# Own_USB-C_Breakout_v3_0_Final_AR.net
KiCad netlist of a schematic drawn in EAGLE
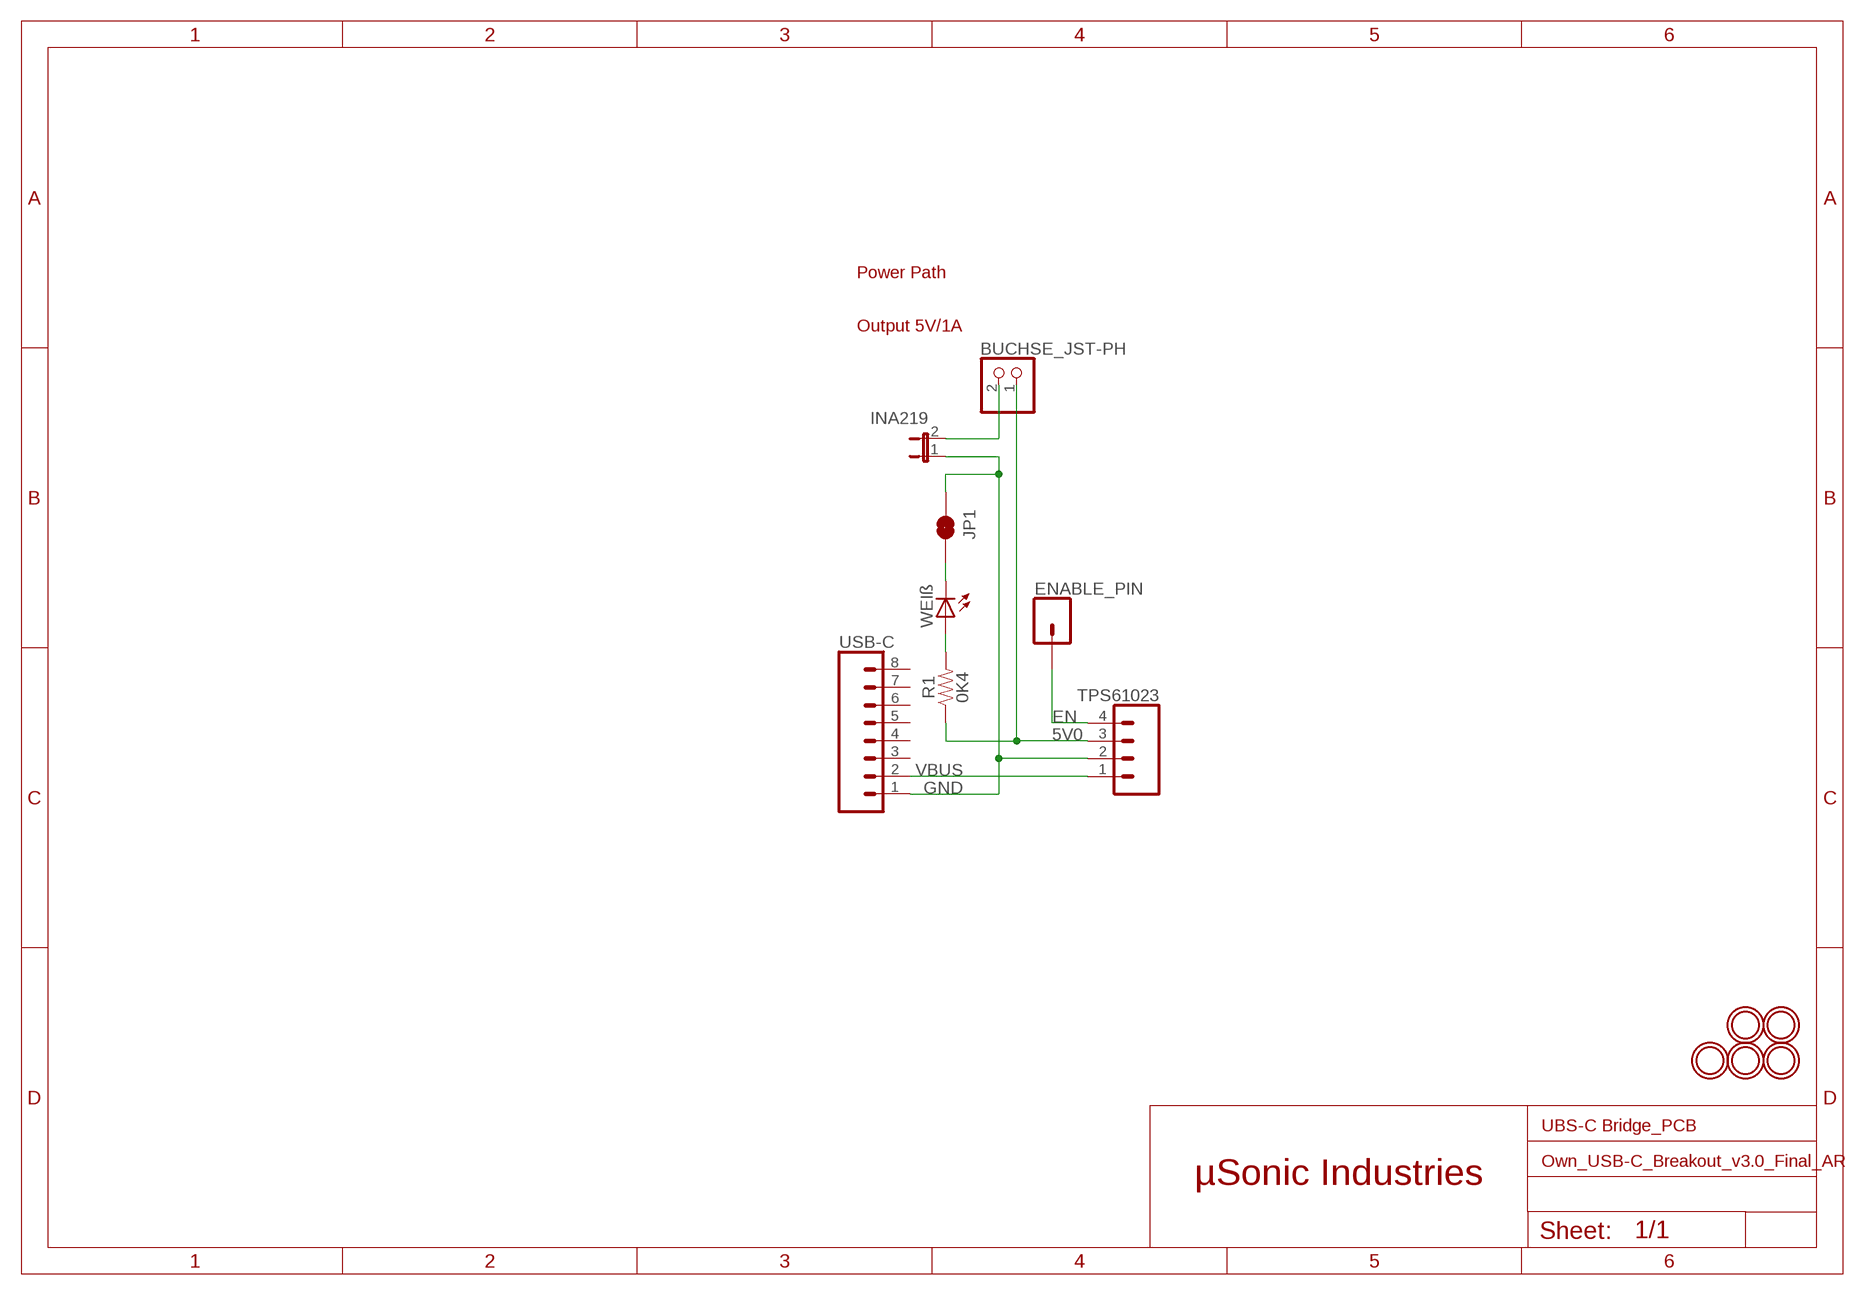
[diagram p0: schematic, sheet 1]

(export (version "E")
  (design (tool "Eeschema 10.0.6"))
  (components
    (comp (ref "BUCHSE_JST-PH")
      (value "JST_2PINOWN")
      (footprint "eagle-import:JST-PH-2-THMOWN")
      (libsource (lib "eagle-import") (part "JST_2PINOWN"))
    )
    (comp (ref "ENABLE_PIN")
      (value "CONN_01PTH_NO_SILK_YES_STOP")
      (footprint "eagle-import:1X01_NO_SILK")
      (libsource (lib "eagle-import") (part "CONN_01PTH_NO_SILK_YES_STOP"))
    )
    (comp (ref "INA219")
      (value "JP1E")
      (footprint "eagle-import:JP1")
      (libsource (lib "eagle-import") (part "JP1E"))
    )
    (comp (ref "JP1")
      (value "JUMPER-SMT_2_NC_TRACE_SILK")
      (footprint "eagle-import:SMT-JUMPER_2_NC_TRACE_SILK")
      (libsource (lib "eagle-import") (part "JUMPER-SMT_2_NC_TRACE_SILK"))
    )
    (comp (ref "R1")
      (value "0K4")
      (footprint "eagle-import:0805")
      (libsource (lib "eagle-import") (part "RESISTOR0805"))
    )
    (comp (ref "TPS61023")
      (value "CONN_041X04_NO_SILK")
      (footprint "eagle-import:1X04_NO_SILK")
      (libsource (lib "eagle-import") (part "CONN_041X04_NO_SILK"))
    )
    (comp (ref "U$1")
      (value "MOUNTINGHOLE2.5")
      (footprint "eagle-import:MOUNTINGHOLE_2.5_PLATED")
      (libsource (lib "eagle-import") (part "MOUNTINGHOLE2.5"))
    )
    (comp (ref "U$2")
      (value "MOUNTINGHOLE2.5")
      (footprint "eagle-import:MOUNTINGHOLE_2.5_PLATED")
      (libsource (lib "eagle-import") (part "MOUNTINGHOLE2.5"))
    )
    (comp (ref "U$10")
      (value "MOUNTINGHOLE2.5")
      (footprint "eagle-import:MOUNTINGHOLE_2.5_PLATED")
      (libsource (lib "eagle-import") (part "MOUNTINGHOLE2.5"))
    )
    (comp (ref "U$11")
      (value "MOUNTINGHOLE2.5")
      (footprint "eagle-import:MOUNTINGHOLE_2.5_PLATED")
      (libsource (lib "eagle-import") (part "MOUNTINGHOLE2.5"))
    )
    (comp (ref "U$14")
      (value "MOUNTINGHOLE2.5")
      (footprint "eagle-import:MOUNTINGHOLE_2.5_PLATED")
      (libsource (lib "eagle-import") (part "MOUNTINGHOLE2.5"))
    )
    (comp (ref "USB-C")
      (value "CONN_08NO_SILK_FEMALE_PTH")
      (footprint "eagle-import:1X08_NO_SILK")
      (libsource (lib "eagle-import") (part "CONN_08NO_SILK_FEMALE_PTH"))
    )
    (comp (ref "WEIß")
      (value "LEDCHIPLED_0805")
      (footprint "eagle-import:CHIPLED_0805")
      (libsource (lib "eagle-import") (part "LEDCHIPLED_0805"))
    )
  )
  (nets
    (net (code "1") (name "/5V0") (class "Default")
      (node (ref "BUCHSE_JST-PH") (pin "1") (pinfunction "2_1") (pintype "passive"))
      (node (ref "R1") (pin "1") (pinfunction "1_1") (pintype "passive"))
      (node (ref "TPS61023") (pin "3") (pinfunction "3_3") (pintype "passive"))
    )
    (net (code "2") (name "/EN") (class "Default")
      (node (ref "ENABLE_PIN") (pin "1") (pinfunction "1_1") (pintype "passive"))
      (node (ref "TPS61023") (pin "4") (pinfunction "4_4") (pintype "passive"))
    )
    (net (code "3") (name "/GND") (class "Default")
      (node (ref "INA219") (pin "1") (pinfunction "1_1") (pintype "passive"))
      (node (ref "JP1") (pin "1") (pinfunction "1_1") (pintype "passive"))
      (node (ref "TPS61023") (pin "2") (pinfunction "2_2") (pintype "passive"))
      (node (ref "USB-C") (pin "1") (pinfunction "1_1") (pintype "passive"))
    )
    (net (code "4") (name "/VBUS") (class "Default")
      (node (ref "TPS61023") (pin "1") (pinfunction "1_1") (pintype "passive"))
      (node (ref "USB-C") (pin "2") (pinfunction "2_2") (pintype "passive"))
    )
    (net (code "5") (name "Net-(BUCHSE_JST-PH-1)") (class "Default")
      (node (ref "BUCHSE_JST-PH") (pin "2") (pinfunction "1_2") (pintype "passive"))
      (node (ref "INA219") (pin "2") (pinfunction "2_2") (pintype "passive"))
    )
    (net (code "6") (name "Net-(JP1-Pad2)") (class "Default")
      (node (ref "JP1") (pin "2") (pinfunction "2_2") (pintype "passive"))
      (node (ref "WEIß") (pin "C") (pinfunction "C_C") (pintype "passive"))
    )
    (net (code "7") (name "Net-(R1-Pad2)") (class "Default")
      (node (ref "R1") (pin "2") (pinfunction "2_2") (pintype "passive"))
      (node (ref "WEIß") (pin "A") (pinfunction "A_A") (pintype "passive"))
    )
    (net (code "8") (name "unconnected-(USB-C-Pad3)") (class "Default")
      (node (ref "USB-C") (pin "3") (pinfunction "3_3") (pintype "passive"))
    )
    (net (code "9") (name "unconnected-(USB-C-Pad4)") (class "Default")
      (node (ref "USB-C") (pin "4") (pinfunction "4_4") (pintype "passive"))
    )
    (net (code "10") (name "unconnected-(USB-C-Pad5)") (class "Default")
      (node (ref "USB-C") (pin "5") (pinfunction "5_5") (pintype "passive"))
    )
    (net (code "11") (name "unconnected-(USB-C-Pad6)") (class "Default")
      (node (ref "USB-C") (pin "6") (pinfunction "6_6") (pintype "passive"))
    )
    (net (code "12") (name "unconnected-(USB-C-Pad7)") (class "Default")
      (node (ref "USB-C") (pin "7") (pinfunction "7_7") (pintype "passive"))
    )
    (net (code "13") (name "unconnected-(USB-C-Pad8)") (class "Default")
      (node (ref "USB-C") (pin "8") (pinfunction "8_8") (pintype "passive"))
    )
  )
)
